# PCEMouse_rev_D.net
KiCad netlist of a schematic drawn in EAGLE
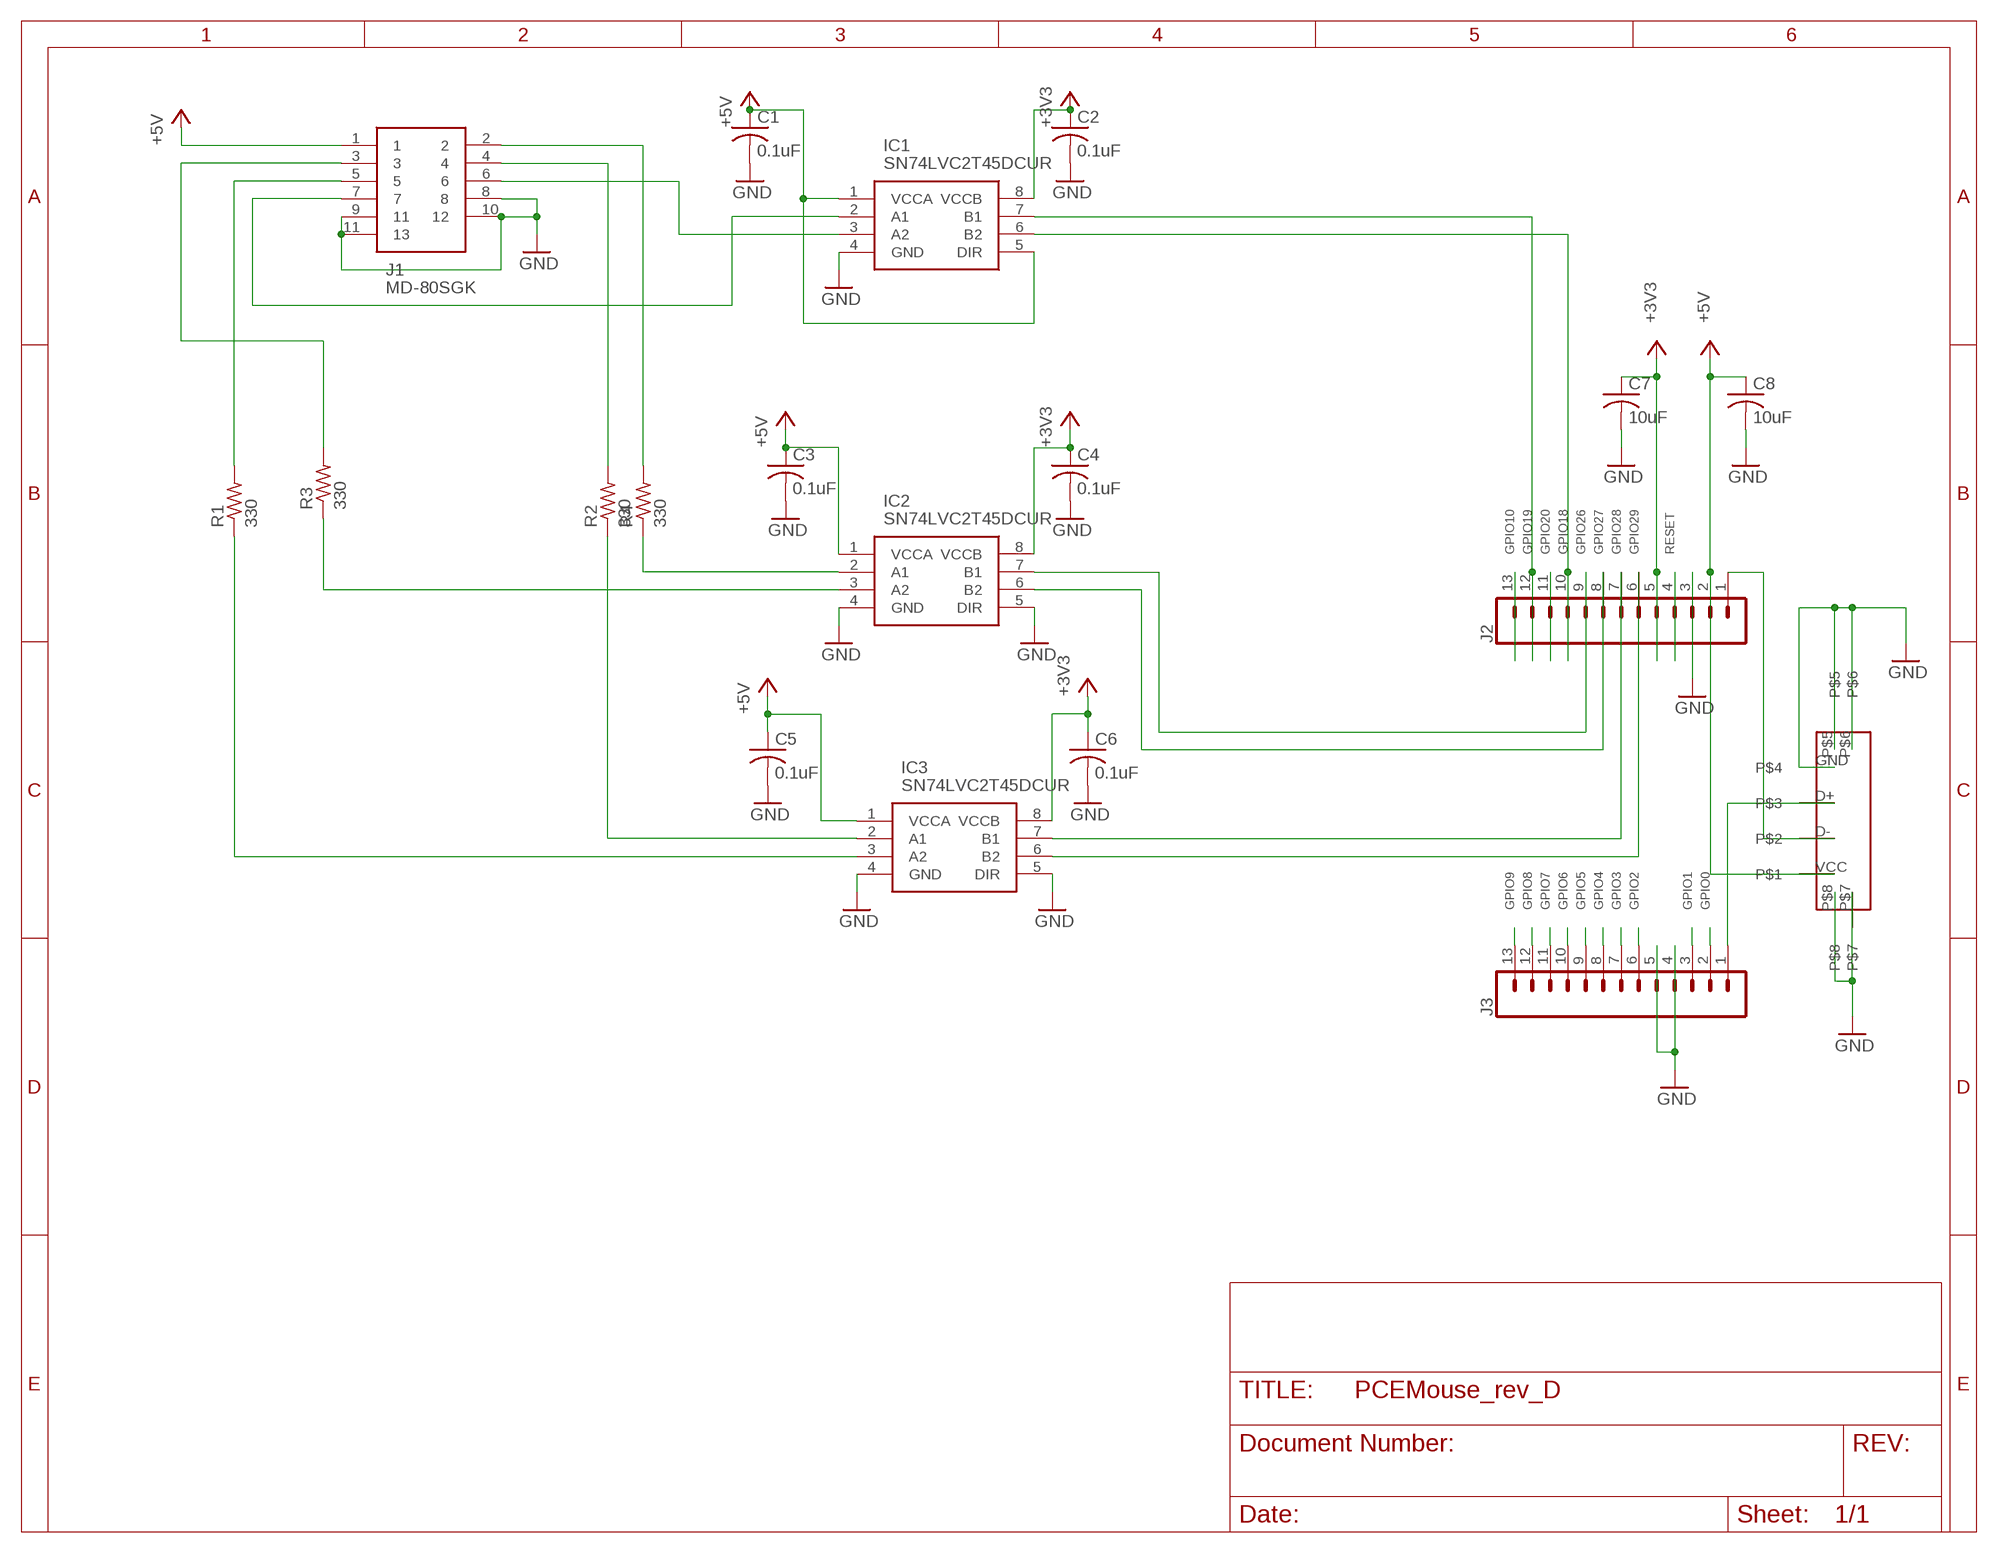
[diagram p0: schematic, sheet 1]

(export (version "E")
  (design (tool "Eeschema 10.0.6"))
  (components
    (comp (ref "C1")
      (value "0.1uF")
      (footprint "eagle-import:C0402")
      (libsource (lib "eagle-import") (part "C-USC0402"))
    )
    (comp (ref "C2")
      (value "0.1uF")
      (footprint "eagle-import:C0402")
      (libsource (lib "eagle-import") (part "C-USC0402"))
    )
    (comp (ref "C3")
      (value "0.1uF")
      (footprint "eagle-import:C0402")
      (libsource (lib "eagle-import") (part "C-USC0402"))
    )
    (comp (ref "C4")
      (value "0.1uF")
      (footprint "eagle-import:C0402")
      (libsource (lib "eagle-import") (part "C-USC0402"))
    )
    (comp (ref "C5")
      (value "0.1uF")
      (footprint "eagle-import:C0402")
      (libsource (lib "eagle-import") (part "C-USC0402"))
    )
    (comp (ref "C6")
      (value "0.1uF")
      (footprint "eagle-import:C0402")
      (libsource (lib "eagle-import") (part "C-USC0402"))
    )
    (comp (ref "C7")
      (value "10uF")
      (footprint "eagle-import:C0805")
      (libsource (lib "eagle-import") (part "resistor_348_C-USC0805"))
    )
    (comp (ref "C8")
      (value "10uF")
      (footprint "eagle-import:C0805")
      (libsource (lib "eagle-import") (part "resistor_348_C-USC0805"))
    )
    (comp (ref "IC1")
      (value "SN74LVC2T45DCUR")
      (footprint "eagle-import:SOP50P310X90-8N")
      (fields (field (name "MOUSER_PART_NUMBER") "595-SN74LVC2T45DCUR"))
      (libsource (lib "eagle-import") (part "SN74LVC2T45DCUR"))
    )
    (comp (ref "IC2")
      (value "SN74LVC2T45DCUR")
      (footprint "eagle-import:SOP50P310X90-8N")
      (fields (field (name "MOUSER_PART_NUMBER") "595-SN74LVC2T45DCUR"))
      (libsource (lib "eagle-import") (part "SN74LVC2T45DCUR"))
    )
    (comp (ref "IC3")
      (value "SN74LVC2T45DCUR")
      (footprint "eagle-import:SOP50P310X90-8N")
      (fields (field (name "MOUSER_PART_NUMBER") "595-SN74LVC2T45DCUR"))
      (libsource (lib "eagle-import") (part "SN74LVC2T45DCUR"))
    )
    (comp (ref "J1")
      (value "MD-80SGK")
      (footprint "eagle-import:MD80SGK")
      (fields (field (name "MOUSER_PART_NUMBER") "490-MD-80SGK"))
      (libsource (lib "eagle-import") (part "MD-80SGK"))
    )
    (comp (ref "J2")
      (value "CONN_13LONGPADS")
      (footprint "eagle-import:1X13-LONGPADS")
      (libsource (lib "eagle-import") (part "CONN_13LONGPADS"))
    )
    (comp (ref "J3")
      (value "CONN_13LONGPADS")
      (footprint "eagle-import:1X13-LONGPADS")
      (libsource (lib "eagle-import") (part "CONN_13LONGPADS"))
    )
    (comp (ref "R1")
      (value "330")
      (footprint "eagle-import:R0402")
      (libsource (lib "eagle-import") (part "R-US_R0402"))
    )
    (comp (ref "R2")
      (value "330")
      (footprint "eagle-import:R0402")
      (libsource (lib "eagle-import") (part "R-US_R0402"))
    )
    (comp (ref "R3")
      (value "330")
      (footprint "eagle-import:R0402")
      (libsource (lib "eagle-import") (part "R-US_R0402"))
    )
    (comp (ref "R4")
      (value "330")
      (footprint "eagle-import:R0402")
      (libsource (lib "eagle-import") (part "R-US_R0402"))
    )
    (comp (ref "U$1")
      (value "PC-ENGINE_912-312A2021S10100")
      (footprint "eagle-import:PC-ENGINE_912-312A2021S10100")
      (libsource (lib "eagle-import") (part "PC-ENGINE_912-312A2021S10100"))
    )
  )
  (nets
    (net (code "1") (name "+3V3") (class "Default")
      (node (ref "C2") (pin "1") (pinfunction "1_1") (pintype "passive"))
      (node (ref "C4") (pin "1") (pinfunction "1_1") (pintype "passive"))
      (node (ref "C6") (pin "1") (pinfunction "1_1") (pintype "passive"))
      (node (ref "C7") (pin "1") (pinfunction "1_1") (pintype "passive"))
      (node (ref "IC1") (pin "8") (pinfunction "VCCB_8") (pintype "bidirectional"))
      (node (ref "IC2") (pin "8") (pinfunction "VCCB_8") (pintype "bidirectional"))
      (node (ref "IC3") (pin "8") (pinfunction "VCCB_8") (pintype "bidirectional"))
      (node (ref "J2") (pin "5") (pinfunction "5_5") (pintype "passive"))
    )
    (net (code "2") (name "+5V") (class "Default")
      (node (ref "C1") (pin "1") (pinfunction "1_1") (pintype "passive"))
      (node (ref "C3") (pin "1") (pinfunction "1_1") (pintype "passive"))
      (node (ref "C5") (pin "1") (pinfunction "1_1") (pintype "passive"))
      (node (ref "C8") (pin "1") (pinfunction "1_1") (pintype "passive"))
      (node (ref "IC1") (pin "1") (pinfunction "VCCA_1") (pintype "bidirectional"))
      (node (ref "IC1") (pin "5") (pinfunction "DIR_5") (pintype "bidirectional"))
      (node (ref "IC2") (pin "1") (pinfunction "VCCA_1") (pintype "bidirectional"))
      (node (ref "IC3") (pin "1") (pinfunction "VCCA_1") (pintype "bidirectional"))
      (node (ref "J1") (pin "1") (pinfunction "1_1") (pintype "bidirectional"))
      (node (ref "J2") (pin "2") (pinfunction "2_2") (pintype "passive"))
      (node (ref "U$1") (pin "VCC") (pinfunction "P$1_VCC") (pintype "bidirectional"))
    )
    (net (code "3") (name "/GPIO0") (class "Default")
      (node (ref "J3") (pin "2") (pinfunction "2_2") (pintype "passive"))
    )
    (net (code "4") (name "/GPIO1") (class "Default")
      (node (ref "J3") (pin "3") (pinfunction "3_3") (pintype "passive"))
    )
    (net (code "5") (name "/GPIO2") (class "Default")
      (node (ref "J3") (pin "6") (pinfunction "6_6") (pintype "passive"))
    )
    (net (code "6") (name "/GPIO3") (class "Default")
      (node (ref "J3") (pin "7") (pinfunction "7_7") (pintype "passive"))
    )
    (net (code "7") (name "/GPIO4") (class "Default")
      (node (ref "J3") (pin "8") (pinfunction "8_8") (pintype "passive"))
    )
    (net (code "8") (name "/GPIO5") (class "Default")
      (node (ref "J3") (pin "9") (pinfunction "9_9") (pintype "passive"))
    )
    (net (code "9") (name "/GPIO6") (class "Default")
      (node (ref "J3") (pin "10") (pinfunction "10_10") (pintype "passive"))
    )
    (net (code "10") (name "/GPIO7") (class "Default")
      (node (ref "J3") (pin "11") (pinfunction "11_11") (pintype "passive"))
    )
    (net (code "11") (name "/GPIO8") (class "Default")
      (node (ref "J3") (pin "12") (pinfunction "12_12") (pintype "passive"))
    )
    (net (code "12") (name "/GPIO9") (class "Default")
      (node (ref "J3") (pin "13") (pinfunction "13_13") (pintype "passive"))
    )
    (net (code "13") (name "/GPIO10") (class "Default")
      (node (ref "J2") (pin "13") (pinfunction "13_13") (pintype "passive"))
    )
    (net (code "14") (name "/GPIO18") (class "Default")
      (node (ref "IC1") (pin "6") (pinfunction "B2_6") (pintype "bidirectional"))
      (node (ref "J2") (pin "10") (pinfunction "10_10") (pintype "passive"))
    )
    (net (code "15") (name "/GPIO19") (class "Default")
      (node (ref "IC1") (pin "7") (pinfunction "B1_7") (pintype "bidirectional"))
      (node (ref "J2") (pin "12") (pinfunction "12_12") (pintype "passive"))
    )
    (net (code "16") (name "/GPIO20") (class "Default")
      (node (ref "J2") (pin "11") (pinfunction "11_11") (pintype "passive"))
    )
    (net (code "17") (name "/GPIO26") (class "Default")
      (node (ref "IC2") (pin "7") (pinfunction "B1_7") (pintype "bidirectional"))
      (node (ref "J2") (pin "9") (pinfunction "9_9") (pintype "passive"))
    )
    (net (code "18") (name "/GPIO27") (class "Default")
      (node (ref "IC2") (pin "6") (pinfunction "B2_6") (pintype "bidirectional"))
      (node (ref "J2") (pin "8") (pinfunction "8_8") (pintype "passive"))
    )
    (net (code "19") (name "/GPIO28") (class "Default")
      (node (ref "IC3") (pin "7") (pinfunction "B1_7") (pintype "bidirectional"))
      (node (ref "J2") (pin "7") (pinfunction "7_7") (pintype "passive"))
    )
    (net (code "20") (name "/GPIO29") (class "Default")
      (node (ref "IC3") (pin "6") (pinfunction "B2_6") (pintype "bidirectional"))
      (node (ref "J2") (pin "6") (pinfunction "6_6") (pintype "passive"))
    )
    (net (code "21") (name "/RESET") (class "Default")
      (node (ref "J2") (pin "4") (pinfunction "4_4") (pintype "passive"))
    )
    (net (code "22") (name "GND") (class "Default")
      (node (ref "C1") (pin "2") (pinfunction "2_2") (pintype "passive"))
      (node (ref "C2") (pin "2") (pinfunction "2_2") (pintype "passive"))
      (node (ref "C3") (pin "2") (pinfunction "2_2") (pintype "passive"))
      (node (ref "C4") (pin "2") (pinfunction "2_2") (pintype "passive"))
      (node (ref "C5") (pin "2") (pinfunction "2_2") (pintype "passive"))
      (node (ref "C6") (pin "2") (pinfunction "2_2") (pintype "passive"))
      (node (ref "C7") (pin "2") (pinfunction "2_2") (pintype "passive"))
      (node (ref "C8") (pin "2") (pinfunction "2_2") (pintype "passive"))
      (node (ref "IC1") (pin "4") (pinfunction "GND_4") (pintype "bidirectional"))
      (node (ref "IC2") (pin "4") (pinfunction "GND_4") (pintype "bidirectional"))
      (node (ref "IC2") (pin "5") (pinfunction "DIR_5") (pintype "bidirectional"))
      (node (ref "IC3") (pin "4") (pinfunction "GND_4") (pintype "bidirectional"))
      (node (ref "IC3") (pin "5") (pinfunction "DIR_5") (pintype "bidirectional"))
      (node (ref "J1") (pin "10") (pinfunction "12_10") (pintype "bidirectional"))
      (node (ref "J1") (pin "11") (pinfunction "13_11") (pintype "bidirectional"))
      (node (ref "J1") (pin "8") (pinfunction "8_8") (pintype "bidirectional"))
      (node (ref "J1") (pin "9") (pinfunction "11_9") (pintype "bidirectional"))
      (node (ref "J2") (pin "3") (pinfunction "3_3") (pintype "passive"))
      (node (ref "J3") (pin "4") (pinfunction "4_4") (pintype "passive"))
      (node (ref "J3") (pin "5") (pinfunction "5_5") (pintype "passive"))
      (node (ref "U$1") (pin "GND") (pinfunction "P$4_GND") (pintype "bidirectional"))
      (node (ref "U$1") (pin "P$5") (pinfunction "P$5_P$5") (pintype "bidirectional"))
      (node (ref "U$1") (pin "P$6") (pinfunction "P$6_P$6") (pintype "bidirectional"))
      (node (ref "U$1") (pin "P$7") (pinfunction "P$7_P$7") (pintype "bidirectional"))
      (node (ref "U$1") (pin "P$8") (pinfunction "P$8_P$8") (pintype "bidirectional"))
    )
    (net (code "23") (name "Net-(IC1-A1)") (class "Default")
      (node (ref "IC1") (pin "2") (pinfunction "A1_2") (pintype "bidirectional"))
      (node (ref "J1") (pin "7") (pinfunction "7_7") (pintype "bidirectional"))
    )
    (net (code "24") (name "Net-(IC1-A2)") (class "Default")
      (node (ref "IC1") (pin "3") (pinfunction "A2_3") (pintype "bidirectional"))
      (node (ref "J1") (pin "6") (pinfunction "6_6") (pintype "bidirectional"))
    )
    (net (code "25") (name "Net-(IC2-A1)") (class "Default")
      (node (ref "IC2") (pin "2") (pinfunction "A1_2") (pintype "bidirectional"))
      (node (ref "R4") (pin "1") (pinfunction "1_1") (pintype "passive"))
    )
    (net (code "26") (name "Net-(IC2-A2)") (class "Default")
      (node (ref "IC2") (pin "3") (pinfunction "A2_3") (pintype "bidirectional"))
      (node (ref "R3") (pin "1") (pinfunction "1_1") (pintype "passive"))
    )
    (net (code "27") (name "Net-(IC3-A1)") (class "Default")
      (node (ref "IC3") (pin "2") (pinfunction "A1_2") (pintype "bidirectional"))
      (node (ref "R2") (pin "1") (pinfunction "1_1") (pintype "passive"))
    )
    (net (code "28") (name "Net-(IC3-A2)") (class "Default")
      (node (ref "IC3") (pin "3") (pinfunction "A2_3") (pintype "bidirectional"))
      (node (ref "R1") (pin "1") (pinfunction "1_1") (pintype "passive"))
    )
    (net (code "29") (name "Net-(J1-Pad2)") (class "Default")
      (node (ref "J1") (pin "2") (pinfunction "2_2") (pintype "bidirectional"))
      (node (ref "R4") (pin "2") (pinfunction "2_2") (pintype "passive"))
    )
    (net (code "30") (name "Net-(J1-Pad3)") (class "Default")
      (node (ref "J1") (pin "3") (pinfunction "3_3") (pintype "bidirectional"))
      (node (ref "R3") (pin "2") (pinfunction "2_2") (pintype "passive"))
    )
    (net (code "31") (name "Net-(J1-Pad4)") (class "Default")
      (node (ref "J1") (pin "4") (pinfunction "4_4") (pintype "bidirectional"))
      (node (ref "R2") (pin "2") (pinfunction "2_2") (pintype "passive"))
    )
    (net (code "32") (name "Net-(J1-Pad5)") (class "Default")
      (node (ref "J1") (pin "5") (pinfunction "5_5") (pintype "bidirectional"))
      (node (ref "R1") (pin "2") (pinfunction "2_2") (pintype "passive"))
    )
    (net (code "33") (name "Net-(U$1-P$2)") (class "Default")
      (node (ref "J2") (pin "1") (pinfunction "1_1") (pintype "passive"))
      (node (ref "U$1") (pin "D-") (pinfunction "P$2_D-") (pintype "bidirectional"))
    )
    (net (code "34") (name "Net-(U$1-P$3)") (class "Default")
      (node (ref "J3") (pin "1") (pinfunction "1_1") (pintype "passive"))
      (node (ref "U$1") (pin "D+") (pinfunction "P$3_D+") (pintype "bidirectional"))
    )
  )
)
